# daughter-pots1_1.net
KiCad netlist of a schematic drawn in EAGLE
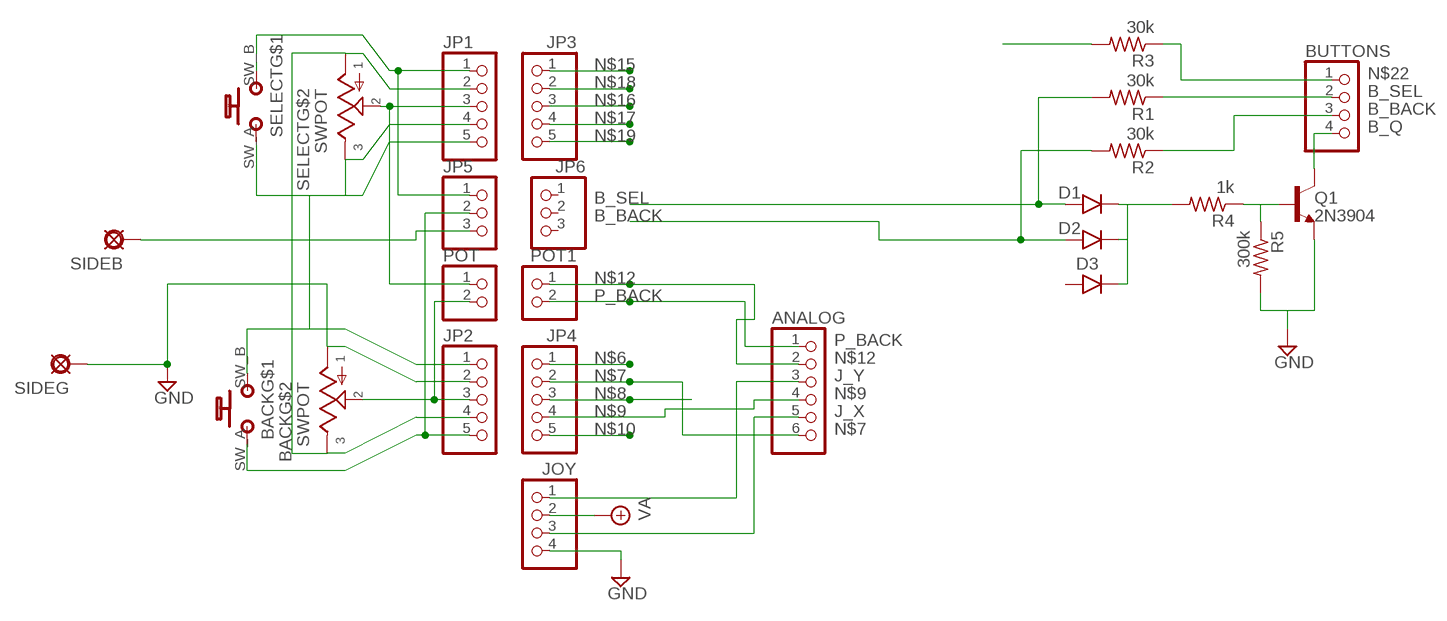
[diagram p0: schematic, sheet 1]

(export (version "E")
  (design (tool "Eeschema 10.0.6"))
  (components
    (comp (ref "ANALOG")
      (value "PINHD-1X6")
      (footprint "eagle-import:1X06")
      (libsource (lib "eagle-import") (part "PINHD-1X6"))
    )
    (comp (ref "BACK")
      (value "SWPOT")
      (footprint "eagle-import:SWPOT")
      (libsource (lib "eagle-import") (part "SWPOT"))
    )
    (comp (ref "BUTTONS")
      (value "PINHD-1X4")
      (footprint "eagle-import:1X04")
      (libsource (lib "eagle-import") (part "PINHD-1X4"))
    )
    (comp (ref "D1")
      (value "1N4148-3")
      (footprint "eagle-import:DO35-3")
      (libsource (lib "eagle-import") (part "1N4148-3"))
    )
    (comp (ref "D2")
      (value "1N4148-2")
      (footprint "eagle-import:DO35-2")
      (libsource (lib "eagle-import") (part "1N4148-2"))
    )
    (comp (ref "D3")
      (value "1N4148-4")
      (footprint "eagle-import:DO35-4")
      (libsource (lib "eagle-import") (part "1N4148-4"))
    )
    (comp (ref "JOY")
      (value "PINHD-1X4")
      (footprint "eagle-import:1X04")
      (libsource (lib "eagle-import") (part "PINHD-1X4"))
    )
    (comp (ref "JP1")
      (value "PINHD-1X5")
      (footprint "eagle-import:1X05")
      (libsource (lib "eagle-import") (part "PINHD-1X5"))
    )
    (comp (ref "JP2")
      (value "PINHD-1X5")
      (footprint "eagle-import:1X05")
      (libsource (lib "eagle-import") (part "PINHD-1X5"))
    )
    (comp (ref "JP3")
      (value "PINHD-1X5")
      (footprint "eagle-import:1X05")
      (libsource (lib "eagle-import") (part "PINHD-1X5"))
    )
    (comp (ref "JP4")
      (value "PINHD-1X5")
      (footprint "eagle-import:1X05")
      (libsource (lib "eagle-import") (part "PINHD-1X5"))
    )
    (comp (ref "JP5")
      (value "PINHD-1X3")
      (footprint "eagle-import:1X03")
      (libsource (lib "eagle-import") (part "PINHD-1X3"))
    )
    (comp (ref "JP6")
      (value "PINHD-1X3")
      (footprint "eagle-import:1X03")
      (libsource (lib "eagle-import") (part "PINHD-1X3"))
    )
    (comp (ref "POT")
      (value "PINHD-1X2")
      (footprint "eagle-import:1X02")
      (libsource (lib "eagle-import") (part "PINHD-1X2"))
    )
    (comp (ref "POT1")
      (value "PINHD-1X2")
      (footprint "eagle-import:1X02")
      (libsource (lib "eagle-import") (part "PINHD-1X2"))
    )
    (comp (ref "Q1")
      (value "2N3904")
      (footprint "eagle-import:TO92-")
      (libsource (lib "eagle-import") (part "2N3904"))
    )
    (comp (ref "R1")
      (value "30k")
      (footprint "eagle-import:R0207_3")
      (libsource (lib "eagle-import") (part "6MM.3"))
    )
    (comp (ref "R2")
      (value "30k")
      (footprint "eagle-import:R0207_3")
      (libsource (lib "eagle-import") (part "6MM.3"))
    )
    (comp (ref "R3")
      (value "30k")
      (footprint "eagle-import:R0207_3")
      (libsource (lib "eagle-import") (part "6MM.3"))
    )
    (comp (ref "R4")
      (value "1k")
      (footprint "eagle-import:R0207_3")
      (libsource (lib "eagle-import") (part "6MM.3"))
    )
    (comp (ref "R5")
      (value "300k")
      (footprint "eagle-import:R0207_1V")
      (libsource (lib "eagle-import") (part "6MM.1"))
    )
    (comp (ref "SELECT")
      (value "SWPOT")
      (footprint "eagle-import:SWPOT")
      (libsource (lib "eagle-import") (part "SWPOT"))
    )
    (comp (ref "SIDEB")
      (value "PAD")
      (footprint "eagle-import:SQUARE")
      (libsource (lib "eagle-import") (part "PAD"))
    )
    (comp (ref "SIDEG")
      (value "PAD")
      (footprint "eagle-import:SQUARE")
      (libsource (lib "eagle-import") (part "PAD"))
    )
  )
  (nets
    (net (code "1") (name "/B_BACK") (class "Default")
      (node (ref "D2") (pin "A") (pinfunction "A_A") (pintype "passive"))
      (node (ref "R2") (pin "2") (pinfunction "2_2") (pintype "passive"))
    )
    (net (code "2") (name "/B_Q") (class "Default")
      (node (ref "BUTTONS") (pin "4") (pinfunction "4_4") (pintype "passive"))
      (node (ref "Q1") (pin "1") (pinfunction "C_1") (pintype "passive"))
    )
    (net (code "3") (name "/B_SEL") (class "Default")
      (node (ref "D1") (pin "A") (pinfunction "A_A") (pintype "passive"))
      (node (ref "R1") (pin "2") (pinfunction "2_2") (pintype "passive"))
    )
    (net (code "4") (name "/J_X") (class "Default")
      (node (ref "ANALOG") (pin "5") (pinfunction "5_5") (pintype "passive"))
      (node (ref "JOY") (pin "3") (pinfunction "3_3") (pintype "passive"))
    )
    (net (code "5") (name "/J_Y") (class "Default")
      (node (ref "ANALOG") (pin "3") (pinfunction "3_3") (pintype "passive"))
      (node (ref "JOY") (pin "1") (pinfunction "1_1") (pintype "passive"))
    )
    (net (code "6") (name "/N$6") (class "Default")
      (node (ref "JP4") (pin "1") (pinfunction "1_1") (pintype "passive"))
    )
    (net (code "7") (name "/N$7") (class "Default")
      (node (ref "ANALOG") (pin "6") (pinfunction "6_6") (pintype "passive"))
      (node (ref "JP4") (pin "2") (pinfunction "2_2") (pintype "passive"))
    )
    (net (code "8") (name "/N$8") (class "Default")
      (node (ref "JP4") (pin "3") (pinfunction "3_3") (pintype "passive"))
    )
    (net (code "9") (name "/N$9") (class "Default")
      (node (ref "ANALOG") (pin "4") (pinfunction "4_4") (pintype "passive"))
      (node (ref "JP4") (pin "4") (pinfunction "4_4") (pintype "passive"))
    )
    (net (code "10") (name "/N$10") (class "Default")
      (node (ref "JP4") (pin "5") (pinfunction "5_5") (pintype "passive"))
    )
    (net (code "11") (name "/N$12") (class "Default")
      (node (ref "ANALOG") (pin "2") (pinfunction "2_2") (pintype "passive"))
      (node (ref "POT1") (pin "1") (pinfunction "1_1") (pintype "passive"))
    )
    (net (code "12") (name "/N$15") (class "Default")
      (node (ref "JP3") (pin "1") (pinfunction "1_1") (pintype "passive"))
    )
    (net (code "13") (name "/N$16") (class "Default")
      (node (ref "JP3") (pin "3") (pinfunction "3_3") (pintype "passive"))
    )
    (net (code "14") (name "/N$17") (class "Default")
      (node (ref "JP3") (pin "4") (pinfunction "4_4") (pintype "passive"))
    )
    (net (code "15") (name "/N$18") (class "Default")
      (node (ref "JP3") (pin "2") (pinfunction "2_2") (pintype "passive"))
    )
    (net (code "16") (name "/N$19") (class "Default")
      (node (ref "JP3") (pin "5") (pinfunction "5_5") (pintype "passive"))
    )
    (net (code "17") (name "/N$22") (class "Default")
      (node (ref "R3") (pin "2") (pinfunction "2_2") (pintype "passive"))
    )
    (net (code "18") (name "/P_BACK") (class "Default")
      (node (ref "ANALOG") (pin "1") (pinfunction "1_1") (pintype "passive"))
      (node (ref "POT1") (pin "2") (pinfunction "2_2") (pintype "passive"))
    )
    (net (code "19") (name "GND") (class "Default")
      (node (ref "BACK") (pin "POT_B") (pinfunction "POT_B_POT_B") (pintype "passive"))
      (node (ref "BACK") (pin "SW_B") (pinfunction "B_B_SW_B") (pintype "passive"))
      (node (ref "JOY") (pin "4") (pinfunction "4_4") (pintype "passive"))
      (node (ref "JP1") (pin "4") (pinfunction "4_4") (pintype "passive"))
      (node (ref "JP1") (pin "5") (pinfunction "5_5") (pintype "passive"))
      (node (ref "JP2") (pin "1") (pinfunction "1_1") (pintype "passive"))
      (node (ref "JP2") (pin "2") (pinfunction "2_2") (pintype "passive"))
      (node (ref "Q1") (pin "3") (pinfunction "E_3") (pintype "passive"))
      (node (ref "R5") (pin "2") (pinfunction "2_2") (pintype "passive"))
      (node (ref "SELECT") (pin "POT_A") (pinfunction "POT_A_POT_A") (pintype "passive"))
      (node (ref "SELECT") (pin "SW_A") (pinfunction "B_A_SW_A") (pintype "passive"))
      (node (ref "SIDEG") (pin "1") (pinfunction "PAD_1") (pintype "passive"))
    )
    (net (code "20") (name "Net-(BACK-PadPOT_A)") (class "Default")
      (node (ref "BACK") (pin "POT_A") (pinfunction "POT_A_POT_A") (pintype "passive"))
      (node (ref "JP1") (pin "2") (pinfunction "2_2") (pintype "passive"))
      (node (ref "JP2") (pin "4") (pinfunction "4_4") (pintype "passive"))
      (node (ref "SELECT") (pin "POT_B") (pinfunction "POT_B_POT_B") (pintype "passive"))
    )
    (net (code "21") (name "Net-(BACK-PadPOT_W)") (class "Default")
      (node (ref "BACK") (pin "POT_W") (pinfunction "POT_W_POT_W") (pintype "passive"))
      (node (ref "JP2") (pin "3") (pinfunction "3_3") (pintype "passive"))
      (node (ref "POT") (pin "2") (pinfunction "2_2") (pintype "passive"))
    )
    (net (code "22") (name "Net-(BACKA-B_A)") (class "Default")
      (node (ref "BACK") (pin "SW_A") (pinfunction "B_A_SW_A") (pintype "passive"))
      (node (ref "JP2") (pin "5") (pinfunction "5_5") (pintype "passive"))
      (node (ref "JP5") (pin "2") (pinfunction "2_2") (pintype "passive"))
    )
    (net (code "23") (name "Net-(BUTTONS-Pad1)") (class "Default")
      (node (ref "BUTTONS") (pin "1") (pinfunction "1_1") (pintype "passive"))
      (node (ref "R3") (pin "1") (pinfunction "1_1") (pintype "passive"))
    )
    (net (code "24") (name "Net-(BUTTONS-Pad2)") (class "Default")
      (node (ref "BUTTONS") (pin "2") (pinfunction "2_2") (pintype "passive"))
      (node (ref "R1") (pin "1") (pinfunction "1_1") (pintype "passive"))
    )
    (net (code "25") (name "Net-(BUTTONS-Pad3)") (class "Default")
      (node (ref "BUTTONS") (pin "3") (pinfunction "3_3") (pintype "passive"))
      (node (ref "R2") (pin "1") (pinfunction "1_1") (pintype "passive"))
    )
    (net (code "26") (name "Net-(D1-PadC)") (class "Default")
      (node (ref "D1") (pin "C") (pinfunction "C_C") (pintype "passive"))
      (node (ref "D2") (pin "C") (pinfunction "C_C") (pintype "passive"))
      (node (ref "D3") (pin "C") (pinfunction "C_C") (pintype "passive"))
      (node (ref "R4") (pin "2") (pinfunction "2_2") (pintype "passive"))
    )
    (net (code "27") (name "Net-(JP1-Pad3)") (class "Default")
      (node (ref "JP1") (pin "3") (pinfunction "3_3") (pintype "passive"))
      (node (ref "POT") (pin "1") (pinfunction "1_1") (pintype "passive"))
      (node (ref "SELECT") (pin "POT_W") (pinfunction "POT_W_POT_W") (pintype "passive"))
    )
    (net (code "28") (name "Net-(Q1-B)") (class "Default")
      (node (ref "Q1") (pin "2") (pinfunction "B_2") (pintype "passive"))
      (node (ref "R4") (pin "1") (pinfunction "1_1") (pintype "passive"))
      (node (ref "R5") (pin "1") (pinfunction "1_1") (pintype "passive"))
    )
    (net (code "29") (name "Net-(SELECTA-B_B)") (class "Default")
      (node (ref "JP1") (pin "1") (pinfunction "1_1") (pintype "passive"))
      (node (ref "JP5") (pin "1") (pinfunction "1_1") (pintype "passive"))
      (node (ref "SELECT") (pin "SW_B") (pinfunction "B_B_SW_B") (pintype "passive"))
    )
    (net (code "30") (name "Net-(SIDEB-PAD)") (class "Default")
      (node (ref "JP5") (pin "3") (pinfunction "3_3") (pintype "passive"))
      (node (ref "SIDEB") (pin "1") (pinfunction "PAD_1") (pintype "passive"))
    )
    (net (code "31") (name "VA") (class "Default")
      (node (ref "JOY") (pin "2") (pinfunction "2_2") (pintype "passive"))
    )
    (net (code "32") (name "unconnected-(D3-PadA)") (class "Default")
      (node (ref "D3") (pin "A") (pinfunction "A_A") (pintype "passive"))
    )
    (net (code "33") (name "unconnected-(JP6-Pad1)") (class "Default")
      (node (ref "JP6") (pin "1") (pinfunction "1_1") (pintype "passive"))
    )
    (net (code "34") (name "unconnected-(JP6-Pad2)") (class "Default")
      (node (ref "JP6") (pin "2") (pinfunction "2_2") (pintype "passive"))
    )
    (net (code "35") (name "unconnected-(JP6-Pad3)") (class "Default")
      (node (ref "JP6") (pin "3") (pinfunction "3_3") (pintype "passive"))
    )
  )
)
